# Supply_HV_ISOL.net
KiCad netlist of a schematic drawn in Altium Designer
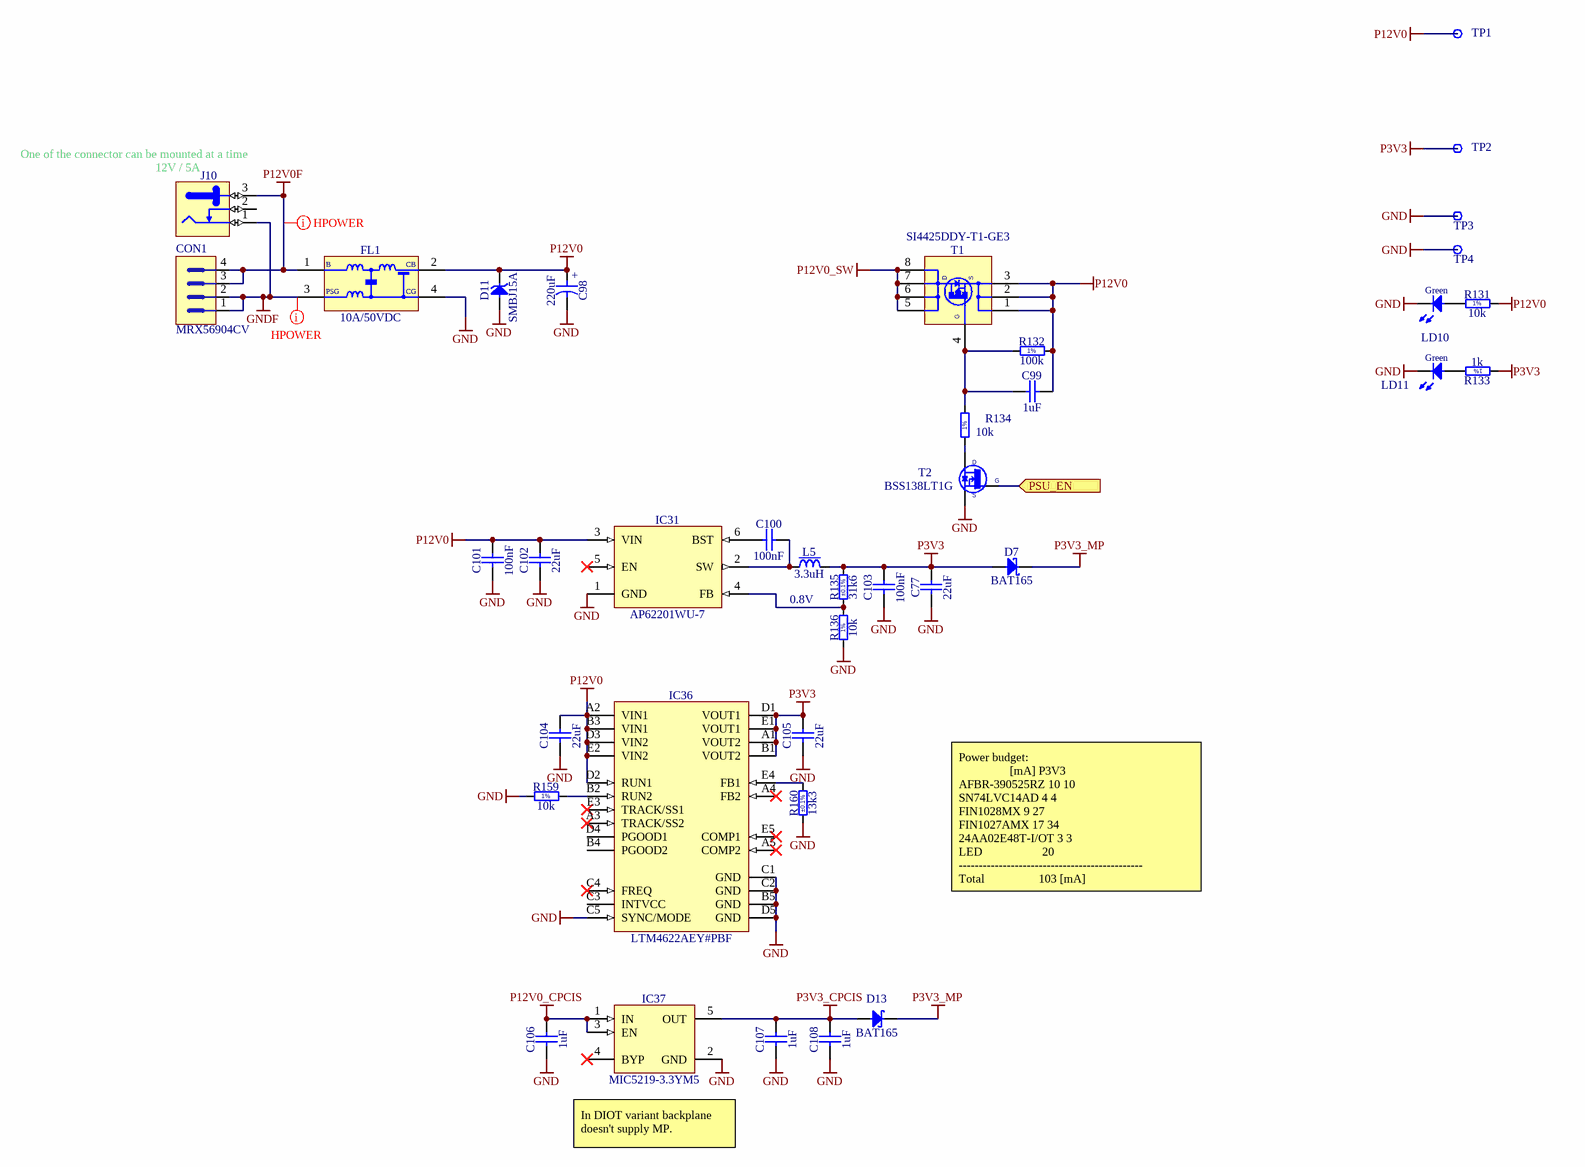
[diagram p0: Supply_HV_ISOL.SchDoc]

(export (version "E")
  (design (tool "Eeschema 10.0.6"))
  (components
    (comp (ref "C77")
      (value "22uF")
      (footprint "CAPC2012X135N")
      (description "Non-polarised capacitor")
      (fields
        (field (name "PART NUMBER") "CC0805_22UF_16V_10%_X5R")
        (field (name "VOLTAGE") "16V")
        (field (name "AUTHOR") "CERN DEM JLC")
      )
      (libsource (lib "Capacitors") (part "Capacitor - non polarized"))
    )
    (comp (ref "C98")
      (value "220uF")
      (footprint "CAPAE830X620N")
      (description "Polarised capacitor")
      (fields
        (field (name "PART NUMBER") "CAE830-620_220UF_16V_20%")
        (field (name "VOLTAGE") "16V")
        (field (name "AUTHOR") "CERN DEM JLC")
      )
      (libsource (lib "Capacitors") (part "Capacitor - polarized"))
    )
    (comp (ref "C99")
      (value "1uF")
      (footprint "CAPC1005X55N")
      (description "Non-polarised capacitor")
      (fields
        (field (name "PART NUMBER") "CC0402_1UF_16V_10%_X5R")
        (field (name "VOLTAGE") "16V")
        (field (name "AUTHOR") "CERN DEM JLC")
      )
      (libsource (lib "Capacitors") (part "Capacitor - non polarized"))
    )
    (comp (ref "C100")
      (value "100nF")
      (footprint "CAPC1005X55N")
      (description "Non-polarised capacitor")
      (fields
        (field (name "PART NUMBER") "CC0402_100NF_16V_10%_X5R")
        (field (name "VOLTAGE") "16V")
        (field (name "AUTHOR") "CERN DEM JLC")
      )
      (libsource (lib "Capacitors") (part "Capacitor - non polarized"))
    )
    (comp (ref "C101")
      (value "100nF")
      (footprint "CAPC1005X55N")
      (description "Non-polarised capacitor")
      (fields
        (field (name "PART NUMBER") "CC0402_100NF_16V_10%_X5R")
        (field (name "VOLTAGE") "16V")
        (field (name "AUTHOR") "CERN DEM JLC")
      )
      (libsource (lib "Capacitors") (part "Capacitor - non polarized"))
    )
    (comp (ref "C102")
      (value "22uF")
      (footprint "CAPC2012X135N")
      (description "Non-polarised capacitor")
      (fields
        (field (name "PART NUMBER") "CC0805_22UF_16V_10%_X5R")
        (field (name "VOLTAGE") "16V")
        (field (name "AUTHOR") "CERN DEM JLC")
      )
      (libsource (lib "Capacitors") (part "Capacitor - non polarized"))
    )
    (comp (ref "C103")
      (value "100nF")
      (footprint "CAPC1005X55N")
      (description "Non-polarised capacitor")
      (fields
        (field (name "PART NUMBER") "CC0402_100NF_16V_10%_X5R")
        (field (name "VOLTAGE") "16V")
        (field (name "AUTHOR") "CERN DEM JLC")
      )
      (libsource (lib "Capacitors") (part "Capacitor - non polarized"))
    )
    (comp (ref "C104")
      (value "22uF")
      (footprint "CAPC2012X135N")
      (description "Non-polarised capacitor")
      (fields
        (field (name "PART NUMBER") "CC0805_22UF_16V_10%_X5R")
        (field (name "VOLTAGE") "16V")
        (field (name "AUTHOR") "CERN DEM JLC")
      )
      (libsource (lib "Capacitors") (part "Capacitor - non polarized"))
    )
    (comp (ref "C105")
      (value "22uF")
      (footprint "CAPC2012X135N")
      (description "Non-polarised capacitor")
      (fields
        (field (name "PART NUMBER") "CC0805_22UF_16V_10%_X5R")
        (field (name "VOLTAGE") "16V")
        (field (name "AUTHOR") "CERN DEM JLC")
      )
      (libsource (lib "Capacitors") (part "Capacitor - non polarized"))
    )
    (comp (ref "C106")
      (value "1uF")
      (footprint "CAPC1608X87N")
      (description "Non-polarised capacitor")
      (fields
        (field (name "PART NUMBER") "CC0603_1UF_25V_10%_X7R")
        (field (name "VOLTAGE") "25V")
        (field (name "AUTHOR") "CERN DEM JLC")
      )
      (libsource (lib "Capacitors") (part "Capacitor - non polarized"))
    )
    (comp (ref "C107")
      (value "1uF")
      (footprint "CAPC1005X55N")
      (description "Non-polarised capacitor")
      (fields
        (field (name "PART NUMBER") "CC0402_1UF_16V_10%_X5R")
        (field (name "VOLTAGE") "16V")
        (field (name "AUTHOR") "CERN DEM JLC")
      )
      (libsource (lib "Capacitors") (part "Capacitor - non polarized"))
    )
    (comp (ref "C108")
      (value "1uF")
      (footprint "CAPC1005X55N")
      (description "Non-polarised capacitor")
      (fields
        (field (name "PART NUMBER") "CC0402_1UF_16V_10%_X5R")
        (field (name "VOLTAGE") "16V")
        (field (name "AUTHOR") "CERN DEM JLC")
      )
      (libsource (lib "Capacitors") (part "Capacitor - non polarized"))
    )
    (comp (ref "CON1")
      (value "MRX56904CV")
      (footprint "MRX56904CV")
      (description "4.2mm cripm terminal header")
      (libsource (lib "LIBRARY_SCH") (part "CON_CRIMP_4.2mm_RA_4"))
    )
    (comp (ref "D7")
      (value "BAT165")
      (footprint "SOD2512X110N")
      (description "Schottky Diode")
      (fields
        (field (name "VOLTAGE") "40V")
        (field (name "POWER") "750mA")
        (field (name "AUTHOR") "CERN DEM JLC")
      )
      (libsource (lib "ICs And Semiconductors") (part "Diode Schottky"))
    )
    (comp (ref "D11")
      (value "SMBJ15A")
      (footprint "DIOM5336X265N")
      (description "Zener Diode")
      (fields
        (field (name "VOLTAGE") "15V")
        (field (name "POWER") "600W")
        (field (name "AUTHOR") "CERN DEM JLC")
      )
      (libsource (lib "ICs And Semiconductors") (part "Diode Zener"))
    )
    (comp (ref "D13")
      (value "BAT165")
      (footprint "SOD2512X110N")
      (description "Schottky Diode")
      (fields
        (field (name "MANUFACTURER") "INFINEON")
        (field (name "VOLTAGE") "40V")
        (field (name "AUTHOR") "CERN DEM JLC")
      )
      (libsource (lib "ICs And Semiconductors") (part "Diode Schottky"))
    )
    (comp (ref "FL1")
      (value "10A/50VDC")
      (footprint "FIL_MURATA_BNX02")
      (description "Block Type EMIFIL (LC Combined)")
      (fields
        (field (name "PART NUMBER") "FIL_MURATA_BNX022-01L")
        (field (name "MANUFACTURER") "MURATA")
        (field (name "AUTHOR") "CERN DEM JLC")
      )
      (libsource (lib "Inductors & Transformers") (part "FIL_MURATA_BNX02"))
    )
    (comp (ref "IC31")
      (value "AP62201WU-7")
      (footprint "SOT95P280X100-6N")
      (description "4.2V TO 18V INPUT, 2A LOW IQ SYNCHRONOUS BUCK CONVERTER")
      (fields (field (name "MANUFACTURER") "DIODES INCORPORATED") (field (name "AUTHOR") "CERN DEM HF"))
      (libsource (lib "ICs And Semiconductors") (part "AP62201WU"))
    )
    (comp (ref "IC36")
      (value "LTM4622AEY#PBF")
      (footprint "BGA25C127P5X5_625X625X262")
      (description "3.6V-20V To 1.5V-12V, Dual 2A or Single 4A  Ultrathin Step-Down DC/DC µModule Regulator")
      (fields (field (name "MANUFACTURER") "LINEAR TECHNOLOGY") (field (name "AUTHOR") "CERN DEM MR"))
      (libsource (lib "ICs And Semiconductors") (part "LTM4622A"))
    )
    (comp (ref "IC37")
      (value "MIC5219-3.3YM5")
      (footprint "SOT95P280X145-5N")
      (description "500mA Peak Output LDO Regulator")
      (fields (field (name "MANUFACTURER") "MICROCHIP TECHNOLOGY") (field (name "AUTHOR") "CERN DEM WB"))
      (libsource (lib "ICs And Semiconductors") (part "MIC5219-X.XYM5"))
    )
    (comp (ref "J10")
      (value "Jack")
      (footprint "SWITCHCRAFT_L712RA")
      (description "24V /3. 5A, 2.1mm Diameter Pin, SMD DC Power Supply Connector With  Break Contact")
      (fields
        (field (name "PART NUMBER") "SWITCHCRAFT_L712RA")
        (field (name "MANUFACTURER") "SWITCHCRAFT")
        (field (name "AUTHOR") "GK")
      )
      (libsource (lib "LIBRARY_SCH") (part "CON_DC_5A_THT_RA"))
    )
    (comp (ref "L5")
      (value "3.3uH")
      (footprint "IND_WURTH_WE-TPC_4828")
      (description "Inductor With Core")
      (fields
        (field (name "PART NUMBER") "IND_3.3UH_30%_WURTH_WE-TPC_744043003")
        (field (name "POWER") "2.15A")
        (field (name "AUTHOR") "CERN DEM JLC")
      )
      (libsource (lib "Inductors & Transformers") (part "Inductor With Magnetic core"))
    )
    (comp (ref "LD10")
      (value "Green")
      (footprint "LED_KINGBRIGHT_KPH-1608CGCK")
      (description "LED Green 1C 2A")
      (fields
        (field (name "PART NUMBER") "LED_KINGBRIGHT_KPH-1608CGCK")
        (field (name "MANUFACTURER") "KINGBRIGHT")
        (field (name "AUTHOR") "CERN DEM JLC")
      )
      (libsource (lib "ICs And Semiconductors") (part "LED Green 1C 2A"))
    )
    (comp (ref "LD11")
      (value "Green")
      (footprint "LED_KINGBRIGHT_KPH-1608CGCK")
      (description "LED Green 1C 2A")
      (fields
        (field (name "PART NUMBER") "LED_KINGBRIGHT_KPH-1608CGCK")
        (field (name "MANUFACTURER") "KINGBRIGHT")
        (field (name "AUTHOR") "CERN DEM JLC")
      )
      (libsource (lib "ICs And Semiconductors") (part "LED Green 1C 2A"))
    )
    (comp (ref "R131")
      (value "10k")
      (footprint "RESC1005X40N")
      (description "Resistor - 1%")
      (fields
        (field (name "PART NUMBER") "R0402_10K_1%_0.0625W_100PPM")
        (field (name "POWER") "0.0625W")
        (field (name "AUTHOR") "CERN DEM JLC")
      )
      (libsource (lib "Resistors") (part "Resistor - 1%"))
    )
    (comp (ref "R132")
      (value "100k")
      (footprint "RESC1608X55N")
      (description "Resistor - 1%")
      (fields
        (field (name "PART NUMBER") "R0603_100K_1%_0.1W_100PPM")
        (field (name "POWER") "0.1W")
        (field (name "AUTHOR") "CERN DEM JLC")
      )
      (libsource (lib "Resistors") (part "Resistor - 1%"))
    )
    (comp (ref "R133")
      (value "1k")
      (footprint "RESC1608X55N")
      (description "Resistor - 1%")
      (fields
        (field (name "PART NUMBER") "R0603_1K_1%_0.1W_100PPM")
        (field (name "POWER") "0.1W")
        (field (name "AUTHOR") "CERN DEM JLC")
      )
      (libsource (lib "Resistors") (part "Resistor - 1%"))
    )
    (comp (ref "R134")
      (value "10k")
      (footprint "RESC1005X40N")
      (description "Resistor - 1%")
      (fields
        (field (name "PART NUMBER") "R0402_10K_1%_0.0625W_100PPM")
        (field (name "POWER") "0.0625W")
        (field (name "AUTHOR") "CERN DEM JLC")
      )
      (libsource (lib "Resistors") (part "Resistor - 1%"))
    )
    (comp (ref "R135")
      (value "31k6")
      (footprint "RESC1005X35N")
      (description "Resistor - 0.1%")
      (fields
        (field (name "TOLERANCE") "±0.1%")
        (field (name "PART NUMBER") "R0402_31K6_0.1%_0.063W_25PPM_YAGEO_RT")
        (field (name "POWER") "0.063W")
        (field (name "AUTHOR") "CERN DEM BC")
      )
      (libsource (lib "Resistors") (part "Resistor - 0.1%"))
    )
    (comp (ref "R136")
      (value "10k")
      (footprint "RESC1005X40N")
      (description "Resistor - 1%")
      (fields
        (field (name "PART NUMBER") "R0402_10K_1%_0.0625W_100PPM")
        (field (name "POWER") "0.0625W")
        (field (name "AUTHOR") "CERN DEM JLC")
      )
      (libsource (lib "Resistors") (part "Resistor - 1%"))
    )
    (comp (ref "R159")
      (value "10k")
      (footprint "RESC1005X40N")
      (description "Resistor - 1%")
      (fields
        (field (name "PART NUMBER") "R0402_10K_1%_0.0625W_100PPM")
        (field (name "POWER") "0.0625W")
        (field (name "AUTHOR") "CERN DEM JLC")
      )
      (libsource (lib "Resistors") (part "Resistor - 1%"))
    )
    (comp (ref "R160")
      (value "13k3")
      (footprint "RESC1608X55N")
      (description "Resistor - 0.1%")
      (fields
        (field (name "TOLERANCE") "±0.1%")
        (field (name "PART NUMBER") "R0603_13K3_0.1%_0.063W_10PPM")
        (field (name "POWER") "0.063W")
        (field (name "AUTHOR") "CERN DEM JLC")
      )
      (libsource (lib "Resistors") (part "Resistor - 0.1%"))
    )
    (comp (ref "T1")
      (value "SI4425DDY-T1-GE3")
      (footprint "SOIC127P600X175-8N")
      (description "-30V -19.7A P-Channel MOSFET")
      (fields (field (name "MANUFACTURER") "VISHAY SILICONIX") (field (name "AUTHOR") "CERN DEM MR"))
      (libsource (lib "ICs And Semiconductors") (part "SI4425DDY"))
    )
    (comp (ref "T2")
      (value "BSS138LT1G")
      (footprint "SOT95P240X110-3N")
      (description "N-CHANNEL MOSFET WITH DIODE")
      (fields (field (name "MANUFACTURER") "ON SEMICONDUCTOR") (field (name "AUTHOR") "CERN DEM JLC"))
      (libsource (lib "ICs And Semiconductors") (part "N-MOSFET-D 1G 2S 3D"))
    )
    (comp (ref "TP1")
      (value "Test Point")
      (footprint "TPS127")
      (fields (field (name "PART NUMBER") "SMD_PAD_1.27X1.27MM") (field (name "AUTHOR") "CERN DEM JLC"))
      (libsource (lib "Eletro-mechanical") (part "Test Point"))
    )
    (comp (ref "TP2")
      (value "Test Point")
      (footprint "TPS127")
      (fields (field (name "PART NUMBER") "SMD_PAD_1.27X1.27MM") (field (name "AUTHOR") "CERN DEM JLC"))
      (libsource (lib "Eletro-mechanical") (part "Test Point"))
    )
    (comp (ref "TP3")
      (value "Test Point")
      (footprint "TPS127")
      (fields (field (name "PART NUMBER") "SMD_PAD_1.27X1.27MM") (field (name "AUTHOR") "CERN DEM JLC"))
      (libsource (lib "Eletro-mechanical") (part "Test Point"))
    )
    (comp (ref "TP4")
      (value "Test Point")
      (footprint "TPS127")
      (fields (field (name "PART NUMBER") "SMD_PAD_1.27X1.27MM") (field (name "AUTHOR") "CERN DEM JLC"))
      (libsource (lib "Eletro-mechanical") (part "Test Point"))
    )
  )
  (nets
    (net (code "1") (name "/PSU_EN") (class "Default")
      (node (ref "T2") (pin "1") (pinfunction "G_1") (pintype "passive"))
    )
    (net (code "2") (name "GND") (class "Default")
      (node (ref "C101") (pin "1") (pinfunction "1_1") (pintype "passive"))
      (node (ref "C102") (pin "1") (pinfunction "1_1") (pintype "passive"))
      (node (ref "C103") (pin "1") (pinfunction "1_1") (pintype "passive"))
      (node (ref "C104") (pin "1") (pinfunction "1_1") (pintype "passive"))
      (node (ref "C105") (pin "1") (pinfunction "1_1") (pintype "passive"))
      (node (ref "C106") (pin "1") (pinfunction "1_1") (pintype "passive"))
      (node (ref "C107") (pin "1") (pinfunction "1_1") (pintype "passive"))
      (node (ref "C108") (pin "1") (pinfunction "1_1") (pintype "passive"))
      (node (ref "C77") (pin "1") (pinfunction "1_1") (pintype "passive"))
      (node (ref "C98") (pin "2") (pinfunction "2_2") (pintype "passive"))
      (node (ref "D11") (pin "2") (pinfunction "A_2") (pintype "passive"))
      (node (ref "FL1") (pin "4") (pinfunction "CG_4") (pintype "passive"))
      (node (ref "IC31") (pin "1") (pinfunction "GND_1") (pintype "power_in"))
      (node (ref "IC36") (pin "B5") (pinfunction "GND_B5") (pintype "power_in"))
      (node (ref "IC36") (pin "C1") (pinfunction "GND_C1") (pintype "power_in"))
      (node (ref "IC36") (pin "C2") (pinfunction "GND_C2") (pintype "power_in"))
      (node (ref "IC36") (pin "C5") (pinfunction "SYNC/MODE_C5") (pintype "input"))
      (node (ref "IC36") (pin "D5") (pinfunction "GND_D5") (pintype "power_in"))
      (node (ref "IC37") (pin "2") (pinfunction "GND_2") (pintype "power_in"))
      (node (ref "LD10") (pin "1") (pinfunction "C_1") (pintype "passive"))
      (node (ref "LD11") (pin "1") (pinfunction "C_1") (pintype "passive"))
      (node (ref "R136") (pin "1") (pinfunction "1_1") (pintype "passive"))
      (node (ref "R159") (pin "1") (pinfunction "1_1") (pintype "passive"))
      (node (ref "R160") (pin "1") (pinfunction "1_1") (pintype "passive"))
      (node (ref "T2") (pin "2") (pinfunction "S_2") (pintype "passive"))
      (node (ref "TP3") (pin "1") (pinfunction "1_1") (pintype "bidirectional"))
      (node (ref "TP4") (pin "1") (pinfunction "1_1") (pintype "bidirectional"))
    )
    (net (code "3") (name "GNDF") (class "Default")
      (node (ref "CON1") (pin "1") (pinfunction "1_1") (pintype "bidirectional"))
      (node (ref "CON1") (pin "2") (pinfunction "2_2") (pintype "bidirectional"))
      (node (ref "FL1") (pin "3") (pinfunction "PSG_3") (pintype "passive"))
      (node (ref "J10") (pin "1") (pinfunction "1_1") (pintype "bidirectional"))
    )
    (net (code "4") (name "Net-(C99-Pad1)") (class "Default")
      (node (ref "C99") (pin "1") (pinfunction "1_1") (pintype "passive"))
      (node (ref "R132") (pin "1") (pinfunction "1_1") (pintype "passive"))
      (node (ref "R134") (pin "2") (pinfunction "2_2") (pintype "passive"))
      (node (ref "T1") (pin "4") (pinfunction "S_4") (pintype "passive"))
    )
    (net (code "5") (name "Net-(IC31-BST)") (class "Default")
      (node (ref "C100") (pin "1") (pinfunction "1_1") (pintype "passive"))
      (node (ref "IC31") (pin "6") (pinfunction "BST_6") (pintype "input"))
    )
    (net (code "6") (name "Net-(IC31-FB)") (class "Default")
      (node (ref "IC31") (pin "4") (pinfunction "FB_4") (pintype "input"))
      (node (ref "R135") (pin "1") (pinfunction "1_1") (pintype "passive"))
      (node (ref "R136") (pin "2") (pinfunction "2_2") (pintype "passive"))
    )
    (net (code "7") (name "Net-(IC31-SW)") (class "Default")
      (node (ref "C100") (pin "2") (pinfunction "2_2") (pintype "passive"))
      (node (ref "IC31") (pin "2") (pinfunction "SW_2") (pintype "output"))
      (node (ref "L5") (pin "1") (pinfunction "1_1") (pintype "passive"))
    )
    (net (code "8") (name "Net-(IC36-FB1)") (class "Default")
      (node (ref "IC36") (pin "E4") (pinfunction "FB1_E4") (pintype "input"))
      (node (ref "R160") (pin "2") (pinfunction "2_2") (pintype "passive"))
    )
    (net (code "9") (name "Net-(IC36-RUN2)") (class "Default")
      (node (ref "IC36") (pin "B2") (pinfunction "RUN2_B2") (pintype "input"))
      (node (ref "R159") (pin "2") (pinfunction "2_2") (pintype "passive"))
    )
    (net (code "10") (name "Net-(LD10-A)") (class "Default")
      (node (ref "LD10") (pin "2") (pinfunction "A_2") (pintype "passive"))
      (node (ref "R131") (pin "1") (pinfunction "1_1") (pintype "passive"))
    )
    (net (code "11") (name "Net-(LD11-A)") (class "Default")
      (node (ref "LD11") (pin "2") (pinfunction "A_2") (pintype "passive"))
      (node (ref "R133") (pin "2") (pinfunction "2_2") (pintype "passive"))
    )
    (net (code "12") (name "Net-(T2-D)") (class "Default")
      (node (ref "R134") (pin "1") (pinfunction "1_1") (pintype "passive"))
      (node (ref "T2") (pin "3") (pinfunction "D_3") (pintype "passive"))
    )
    (net (code "13") (name "P3V3") (class "Default")
      (node (ref "C103") (pin "2") (pinfunction "2_2") (pintype "passive"))
      (node (ref "C105") (pin "2") (pinfunction "2_2") (pintype "passive"))
      (node (ref "C77") (pin "2") (pinfunction "2_2") (pintype "passive"))
      (node (ref "D7") (pin "2") (pinfunction "A_2") (pintype "passive"))
      (node (ref "IC36") (pin "A1") (pinfunction "VOUT2_A1") (pintype "power_in"))
      (node (ref "IC36") (pin "B1") (pinfunction "VOUT2_B1") (pintype "power_in"))
      (node (ref "IC36") (pin "D1") (pinfunction "VOUT1_D1") (pintype "power_in"))
      (node (ref "IC36") (pin "E1") (pinfunction "VOUT1_E1") (pintype "power_in"))
      (node (ref "L5") (pin "2") (pinfunction "2_2") (pintype "passive"))
      (node (ref "R133") (pin "1") (pinfunction "1_1") (pintype "passive"))
      (node (ref "R135") (pin "2") (pinfunction "2_2") (pintype "passive"))
      (node (ref "TP2") (pin "1") (pinfunction "1_1") (pintype "bidirectional"))
    )
    (net (code "14") (name "P3V3_CPCIS") (class "Default")
      (node (ref "C107") (pin "2") (pinfunction "2_2") (pintype "passive"))
      (node (ref "C108") (pin "2") (pinfunction "2_2") (pintype "passive"))
      (node (ref "D13") (pin "2") (pinfunction "A_2") (pintype "passive"))
      (node (ref "IC37") (pin "5") (pinfunction "OUT_5") (pintype "power_in"))
    )
    (net (code "15") (name "P3V3_MP") (class "Default")
      (node (ref "D13") (pin "1") (pinfunction "C_1") (pintype "passive"))
      (node (ref "D7") (pin "1") (pinfunction "C_1") (pintype "passive"))
    )
    (net (code "16") (name "P12V0") (class "Default")
      (node (ref "C101") (pin "2") (pinfunction "2_2") (pintype "passive"))
      (node (ref "C102") (pin "2") (pinfunction "2_2") (pintype "passive"))
      (node (ref "C104") (pin "2") (pinfunction "2_2") (pintype "passive"))
      (node (ref "C98") (pin "1") (pinfunction "1_1") (pintype "passive"))
      (node (ref "C99") (pin "2") (pinfunction "2_2") (pintype "passive"))
      (node (ref "D11") (pin "1") (pinfunction "C_1") (pintype "passive"))
      (node (ref "FL1") (pin "2") (pinfunction "CB_2") (pintype "passive"))
      (node (ref "IC31") (pin "3") (pinfunction "VIN_3") (pintype "input"))
      (node (ref "IC36") (pin "A2") (pinfunction "VIN1_A2") (pintype "power_in"))
      (node (ref "IC36") (pin "B3") (pinfunction "VIN1_B3") (pintype "power_in"))
      (node (ref "IC36") (pin "D2") (pinfunction "RUN1_D2") (pintype "input"))
      (node (ref "IC36") (pin "D3") (pinfunction "VIN2_D3") (pintype "power_in"))
      (node (ref "IC36") (pin "E2") (pinfunction "VIN2_E2") (pintype "power_in"))
      (node (ref "R131") (pin "2") (pinfunction "2_2") (pintype "passive"))
      (node (ref "R132") (pin "2") (pinfunction "2_2") (pintype "passive"))
      (node (ref "T1") (pin "1") (pinfunction "S_1") (pintype "passive"))
      (node (ref "T1") (pin "2") (pinfunction "S_2") (pintype "passive"))
      (node (ref "T1") (pin "3") (pinfunction "S_3") (pintype "passive"))
      (node (ref "TP1") (pin "1") (pinfunction "1_1") (pintype "bidirectional"))
    )
    (net (code "17") (name "P12V0F") (class "Default")
      (node (ref "CON1") (pin "3") (pinfunction "3_3") (pintype "bidirectional"))
      (node (ref "CON1") (pin "4") (pinfunction "4_4") (pintype "bidirectional"))
      (node (ref "FL1") (pin "1") (pinfunction "B_1") (pintype "passive"))
      (node (ref "J10") (pin "3") (pinfunction "3_3") (pintype "bidirectional"))
    )
    (net (code "18") (name "P12V0_CPCIS") (class "Default")
      (node (ref "C106") (pin "2") (pinfunction "2_2") (pintype "passive"))
      (node (ref "IC37") (pin "1") (pinfunction "IN_1") (pintype "input"))
      (node (ref "IC37") (pin "3") (pinfunction "EN_3") (pintype "input"))
    )
    (net (code "19") (name "P12V0_SW") (class "Default")
      (node (ref "T1") (pin "5") (pinfunction "D_5") (pintype "passive"))
      (node (ref "T1") (pin "6") (pinfunction "D_6") (pintype "passive"))
      (node (ref "T1") (pin "7") (pinfunction "D_7") (pintype "passive"))
      (node (ref "T1") (pin "8") (pinfunction "D_8") (pintype "passive"))
    )
    (net (code "20") (name "unconnected-(IC31-EN-Pad5)") (class "Default")
      (node (ref "IC31") (pin "5") (pinfunction "EN_5") (pintype "input+no_connect"))
    )
    (net (code "21") (name "unconnected-(IC36-COMP1-PadE5)") (class "Default")
      (node (ref "IC36") (pin "E5") (pinfunction "COMP1_E5") (pintype "input+no_connect"))
    )
    (net (code "22") (name "unconnected-(IC36-COMP2-PadA5)") (class "Default")
      (node (ref "IC36") (pin "A5") (pinfunction "COMP2_A5") (pintype "input+no_connect"))
    )
    (net (code "23") (name "unconnected-(IC36-FB2-PadA4)") (class "Default")
      (node (ref "IC36") (pin "A4") (pinfunction "FB2_A4") (pintype "input+no_connect"))
    )
    (net (code "24") (name "unconnected-(IC36-FREQ-PadC4)") (class "Default")
      (node (ref "IC36") (pin "C4") (pinfunction "FREQ_C4") (pintype "input+no_connect"))
    )
    (net (code "25") (name "unconnected-(IC36-INTVCC-PadC3)") (class "Default")
      (node (ref "IC36") (pin "C3") (pinfunction "INTVCC_C3") (pintype "power_in"))
    )
    (net (code "26") (name "unconnected-(IC36-PGOOD1-PadD4)") (class "Default")
      (node (ref "IC36") (pin "D4") (pinfunction "PGOOD1_D4") (pintype "open_collector"))
    )
    (net (code "27") (name "unconnected-(IC36-PGOOD2-PadB4)") (class "Default")
      (node (ref "IC36") (pin "B4") (pinfunction "PGOOD2_B4") (pintype "open_collector"))
    )
    (net (code "28") (name "unconnected-(IC36-TRACK{slash}SS1-PadE3)") (class "Default")
      (node (ref "IC36") (pin "E3") (pinfunction "TRACK/SS1_E3") (pintype "input+no_connect"))
    )
    (net (code "29") (name "unconnected-(IC36-TRACK{slash}SS2-PadA3)") (class "Default")
      (node (ref "IC36") (pin "A3") (pinfunction "TRACK/SS2_A3") (pintype "input+no_connect"))
    )
    (net (code "30") (name "unconnected-(IC37-BYP-Pad4)") (class "Default")
      (node (ref "IC37") (pin "4") (pinfunction "BYP_4") (pintype "passive+no_connect"))
    )
    (net (code "31") (name "unconnected-(J10-Pad2)") (class "Default")
      (node (ref "J10") (pin "2") (pinfunction "2_2") (pintype "bidirectional"))
    )
  )
)
